# 9VPart.net
KiCad netlist of a schematic drawn in EAGLE
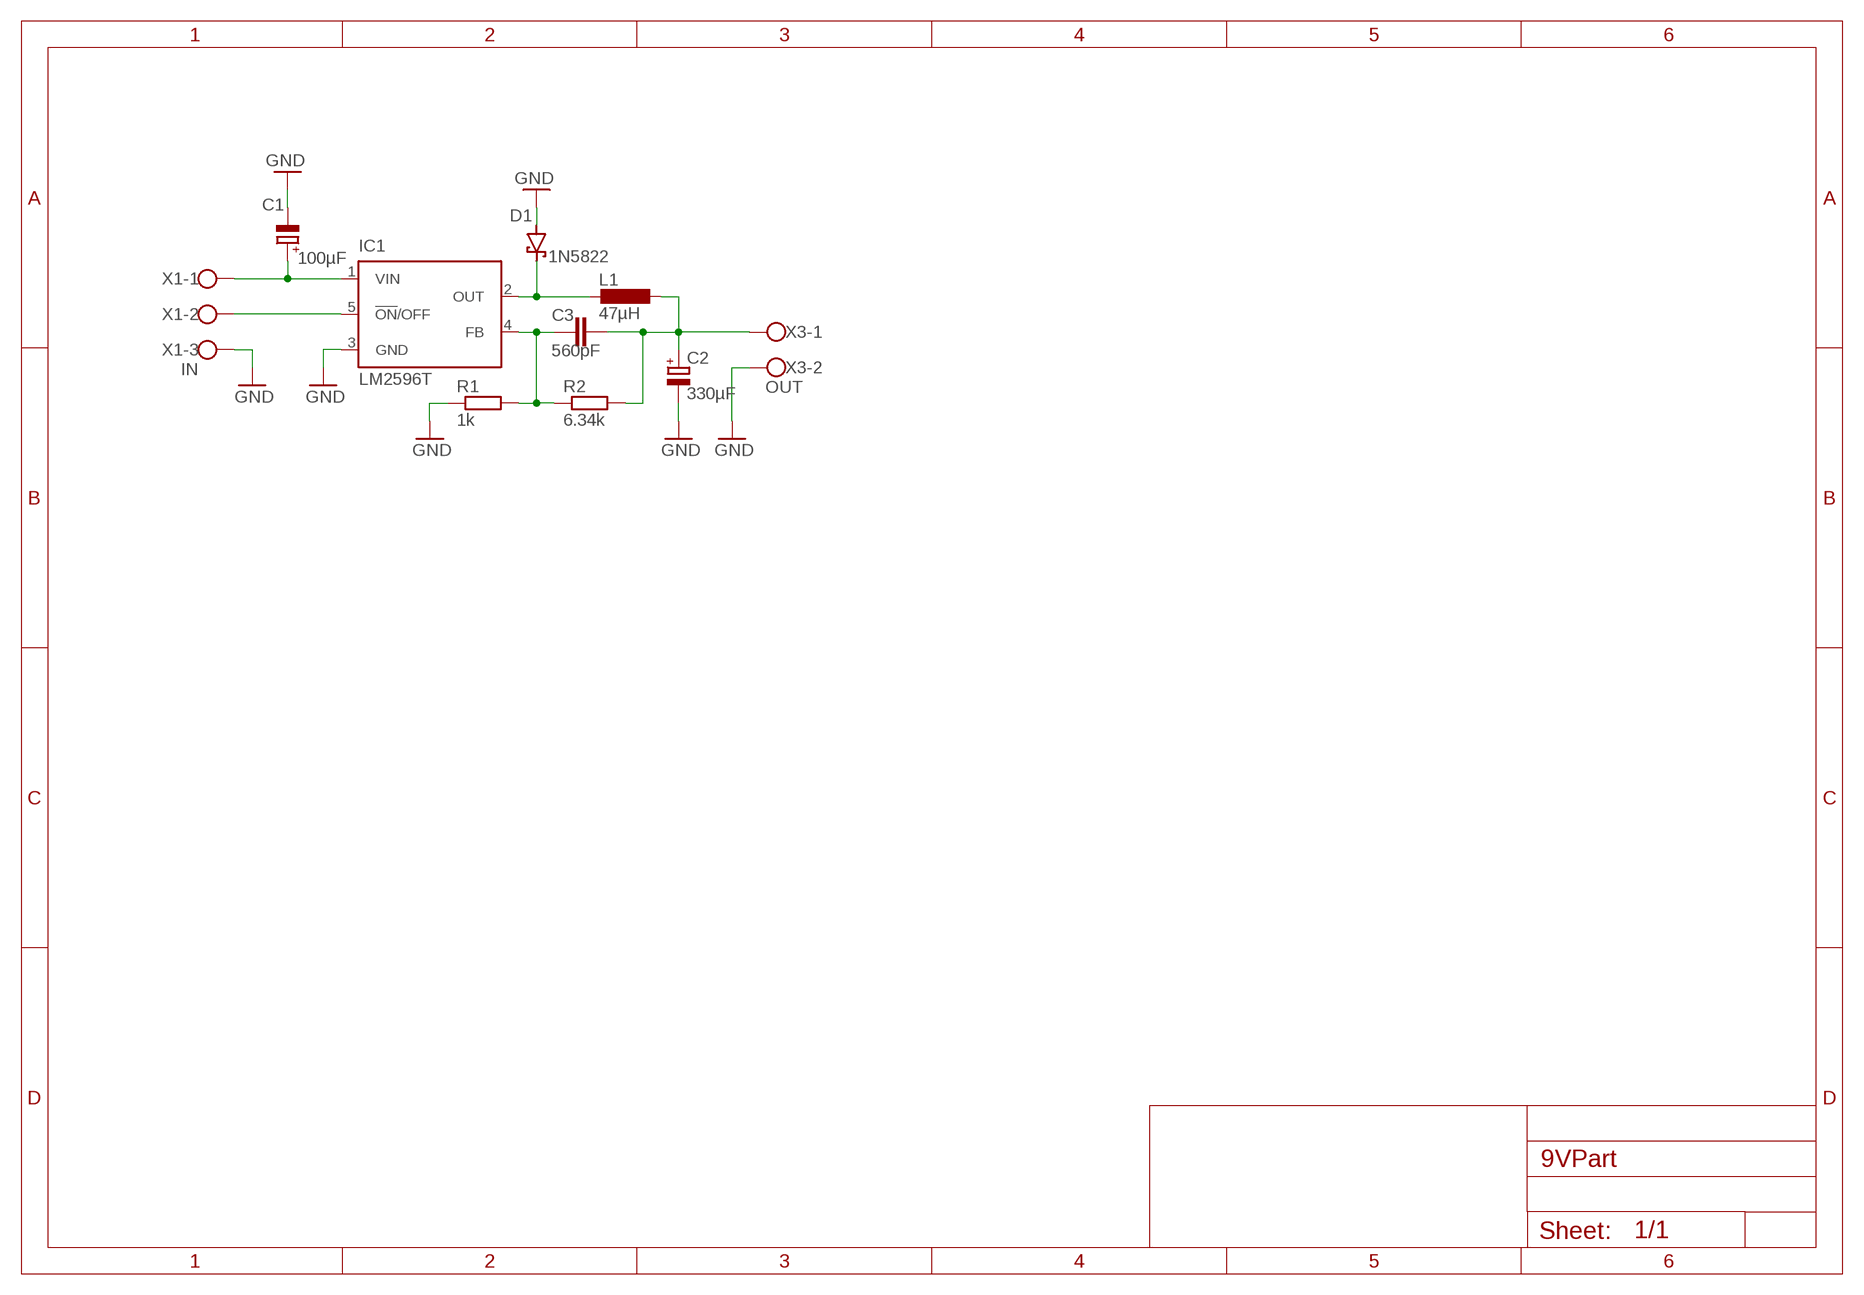
[diagram p0: schematic, sheet 1]

(export (version "E")
  (design (tool "Eeschema 10.0.6"))
  (components
    (comp (ref "C1")
      (value "100µF")
      (footprint "eagle-import:E2,5-6")
      (libsource (lib "eagle-import") (part "CPOL-EUE2.5-6"))
    )
    (comp (ref "C2")
      (value "330µF")
      (footprint "eagle-import:E3,5-8")
      (libsource (lib "eagle-import") (part "CPOL-EUE3.5-8"))
    )
    (comp (ref "C3")
      (value "560pF")
      (footprint "eagle-import:C050-024X044")
      (libsource (lib "eagle-import") (part "C-EU050-024X044"))
    )
    (comp (ref "D1")
      (value "1N5822")
      (footprint "eagle-import:C4111-15")
      (libsource (lib "eagle-import") (part "SCHOTTKY-DIODEC4111-15"))
    )
    (comp (ref "IC1")
      (value "LM2596T")
      (footprint "eagle-import:T05D")
      (fields (field (name "MPN") "LM2596T-ADJ/LF02"))
      (libsource (lib "eagle-import") (part "LM2596T"))
    )
    (comp (ref "L1")
      (value "47µH")
      (footprint "eagle-import:TJ3-U2")
      (libsource (lib "eagle-import") (part "L-EUTJ3-U2"))
    )
    (comp (ref "R1")
      (value "1k")
      (footprint "eagle-import:0207_10")
      (libsource (lib "eagle-import") (part "R-EU_0207/10"))
    )
    (comp (ref "R2")
      (value "6.34k")
      (footprint "eagle-import:0207_10")
      (libsource (lib "eagle-import") (part "R-EU_0207/10"))
    )
    (comp (ref "X1")
      (value "IN")
      (footprint "eagle-import:W237-103")
      (fields (field (name "MPN") "237-103"))
      (libsource (lib "eagle-import") (part "W237-103"))
    )
    (comp (ref "X3")
      (value "OUT")
      (footprint "eagle-import:W237-102")
      (fields (field (name "MPN") "237-102"))
      (libsource (lib "eagle-import") (part "W237-102"))
    )
  )
  (nets
    (net (code "1") (name "GND") (class "Default")
      (node (ref "C1") (pin "-") (pinfunction "-_-") (pintype "passive"))
      (node (ref "C2") (pin "-") (pinfunction "-_-") (pintype "passive"))
      (node (ref "D1") (pin "A") (pinfunction "A_A") (pintype "passive"))
      (node (ref "IC1") (pin "3") (pinfunction "GND_3") (pintype "power_in"))
      (node (ref "R1") (pin "1") (pinfunction "1_1") (pintype "passive"))
      (node (ref "X1") (pin "3") (pinfunction "KL_3") (pintype "passive"))
      (node (ref "X3") (pin "2") (pinfunction "KL_2") (pintype "passive"))
    )
    (net (code "2") (name "Net-(IC1-FB)") (class "Default")
      (node (ref "C3") (pin "1") (pinfunction "1_1") (pintype "passive"))
      (node (ref "IC1") (pin "4") (pinfunction "FB_4") (pintype "input"))
      (node (ref "R1") (pin "2") (pinfunction "2_2") (pintype "passive"))
      (node (ref "R2") (pin "1") (pinfunction "1_1") (pintype "passive"))
    )
    (net (code "3") (name "Net-(IC1-OUT)") (class "Default")
      (node (ref "D1") (pin "C") (pinfunction "C_C") (pintype "passive"))
      (node (ref "IC1") (pin "2") (pinfunction "OUT_2") (pintype "output"))
      (node (ref "L1") (pin "2") (pinfunction "2_2") (pintype "passive"))
    )
    (net (code "4") (name "Net-(IC1-VIN)") (class "Default")
      (node (ref "C1") (pin "+") (pinfunction "+_+") (pintype "passive"))
      (node (ref "IC1") (pin "1") (pinfunction "VIN_1") (pintype "input"))
      (node (ref "X1") (pin "1") (pinfunction "KL_1") (pintype "passive"))
    )
    (net (code "5") (name "Net-(IC1-~{ON}{slash}OFF)") (class "Default")
      (node (ref "IC1") (pin "5") (pinfunction "~{ON}/OFF_5") (pintype "input"))
      (node (ref "X1") (pin "2") (pinfunction "KL_2") (pintype "passive"))
    )
    (net (code "6") (name "Net-(X3A-KL)") (class "Default")
      (node (ref "C2") (pin "+") (pinfunction "+_+") (pintype "passive"))
      (node (ref "C3") (pin "2") (pinfunction "2_2") (pintype "passive"))
      (node (ref "L1") (pin "1") (pinfunction "1_1") (pintype "passive"))
      (node (ref "R2") (pin "2") (pinfunction "2_2") (pintype "passive"))
      (node (ref "X3") (pin "1") (pinfunction "KL_1") (pintype "passive"))
    )
  )
)
